# Battery_Pack_Protection.net
KiCad netlist of a schematic drawn in Altium Designer
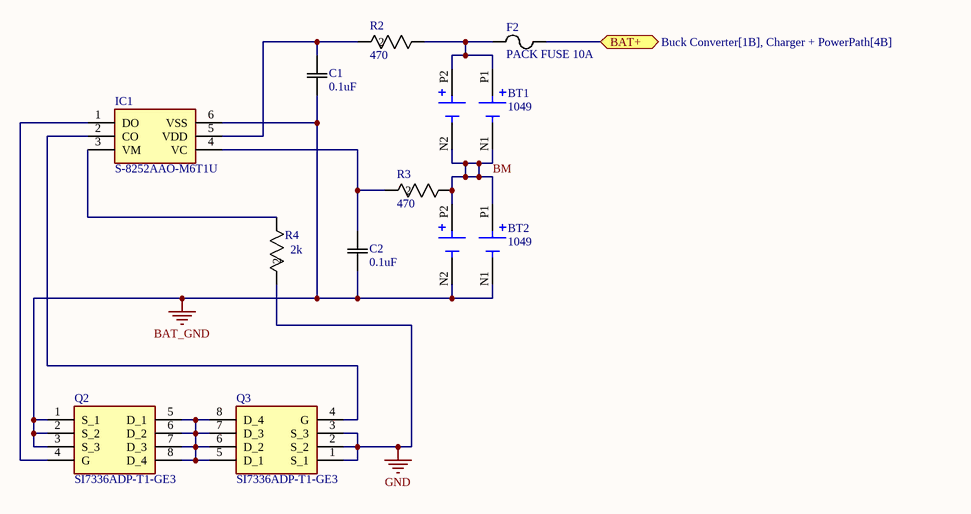
[diagram p0: Battery Pack + Protection.SchDoc]

(export (version "E")
  (design (tool "Eeschema 10.0.6"))
  (components
    (comp (ref "BT1")
      (value "1049")
      (footprint "BAT_1049")
      (description "THM Holder for Dual 18650 Batteries")
      (fields (field (name "MF") "Keystone Electronics"))
      (libsource (lib "1049") (part "1049"))
    )
    (comp (ref "BT2")
      (value "1049")
      (footprint "BAT_1049")
      (description "THM Holder for Dual 18650 Batteries")
      (fields (field (name "MF") "Keystone Electronics"))
      (libsource (lib "1049") (part "1049"))
    )
    (comp (ref "C1")
      (value "0.1uF")
      (footprint "CAPC220145_88N_KEM")
      (description "SMD Comm X7R, Ceramic, 0.1 uF, 10%, 50 VDC, X7R, SMD, MLCC, Temperature Stable, Class II, 0805")
      (fields
        (field (name "MANUFACTURER_PART_NUMBER") "C0805C104K5RACTU")
        (field (name "COPYRIGHT") "Copyright (C) 2025 Ultra Librarian. All rights reserved.")
      )
      (libsource (lib "C0805C104K5RACTU") (part "C0805C104K5RACTU"))
    )
    (comp (ref "C2")
      (value "0.1uF")
      (footprint "CAPC220145_88N_KEM")
      (description "SMD Comm X7R, Ceramic, 0.1 uF, 10%, 50 VDC, X7R, SMD, MLCC, Temperature Stable, Class II, 0805")
      (fields
        (field (name "MANUFACTURER_PART_NUMBER") "C0805C104K5RACTU")
        (field (name "COPYRIGHT") "Copyright (C) 2025 Ultra Librarian. All rights reserved.")
      )
      (libsource (lib "C0805C104K5RACTU") (part "C0805C104K5RACTU"))
    )
    (comp (ref "F2")
      (value "PACK FUSE 10A")
      (footprint "FUSE_2920L70012_LTF")
      (description "Description")
      (fields
        (field (name "MANUFACTURER_PART_NUMBER") "2920L700/12MR-A")
        (field (name "COPYRIGHT") "Copyright (C) 2025 Ultra Librarian. All rights reserved.")
      )
      (libsource (lib "2920L70012MR-A") (part "2920L70012MR-A"))
    )
    (comp (ref "IC1")
      (value "S-8252AAO-M6T1U")
      (footprint "SamacSys:SOT95P275X135-6N")
      (description "Integrated Circuit")
      (fields (field (name "MOUSER PART NUMBER") "628-S-8252AAO-M6T1U"))
      (libsource (lib "*") (part "S-8252AAO-M6T1U"))
    )
    (comp (ref "Q2")
      (value "SI7336ADP-T1-GE3")
      (footprint "SamacSys:SI7141DPT1GE3")
      (description "MOSFET (N-Channel)")
      (fields (field (name "MOUSER PART NUMBER") "781-SI7336ADP-GE3"))
      (libsource (lib "*") (part "SI7336ADP-T1-GE3"))
    )
    (comp (ref "Q3")
      (value "SI7336ADP-T1-GE3")
      (footprint "SamacSys:SI7141DPT1GE3")
      (description "MOSFET (N-Channel)")
      (fields (field (name "MOUSER PART NUMBER") "781-SI7336ADP-GE3"))
      (libsource (lib "") (part "SI7336ADP-T1-GE3_1"))
    )
    (comp (ref "R2")
      (value "470")
      (footprint "RC0805N_YAG")
      (description "Description")
      (fields
        (field (name "MANUFACTURER_PART_NUMBER") "RC0805FR-07470RL")
        (field (name "COPYRIGHT") "Copyright (C) 2025 Ultra Librarian. All rights reserved.")
      )
      (libsource (lib "RC0805FR-07470RL") (part "RC0805FR-07470RL"))
    )
    (comp (ref "R3")
      (value "470")
      (footprint "RC0805N_YAG")
      (description "Description")
      (fields
        (field (name "MANUFACTURER_PART_NUMBER") "RC0805FR-07470RL")
        (field (name "COPYRIGHT") "Copyright (C) 2025 Ultra Librarian. All rights reserved.")
      )
      (libsource (lib "RC0805FR-07470RL") (part "RC0805FR-07470RL"))
    )
    (comp (ref "R4")
      (value "2k")
      (footprint "RC0805N_YAG")
      (description "No Description Available")
      (fields
        (field (name "MANUFACTURER_PART_NUMBER") "RT0805FRE072KL")
        (field (name "COPYRIGHT") "Copyright (C) 2025 Ultra Librarian. All rights reserved.")
      )
      (libsource (lib "RT0805FRE072KL") (part "RT0805FRE072KL"))
    )
  )
  (nets
    (net (code "1") (name "/BAT+") (class "Default")
      (node (ref "F2") (pin "2") (pinfunction "2_2") (pintype "passive"))
    )
    (net (code "2") (name "/BM") (class "Default")
      (node (ref "BT1") (pin "N1") (pinfunction "NEG1_N1") (pintype "passive"))
      (node (ref "BT1") (pin "N2") (pinfunction "NEG2_N2") (pintype "passive"))
      (node (ref "BT2") (pin "P1") (pinfunction "POS1_P1") (pintype "passive"))
      (node (ref "BT2") (pin "P2") (pinfunction "POS2_P2") (pintype "passive"))
      (node (ref "R3") (pin "1") (pinfunction "1_1") (pintype "passive"))
    )
    (net (code "3") (name "BAT_GND") (class "Default")
      (node (ref "BT2") (pin "N1") (pinfunction "NEG1_N1") (pintype "passive"))
      (node (ref "BT2") (pin "N2") (pinfunction "NEG2_N2") (pintype "passive"))
      (node (ref "C1") (pin "1") (pinfunction "1_1") (pintype "passive"))
      (node (ref "C2") (pin "1") (pinfunction "1_1") (pintype "passive"))
      (node (ref "IC1") (pin "6") (pinfunction "VSS_6") (pintype "passive"))
      (node (ref "Q2") (pin "1") (pinfunction "S_1_1") (pintype "passive"))
      (node (ref "Q2") (pin "2") (pinfunction "S_2_2") (pintype "passive"))
      (node (ref "Q2") (pin "3") (pinfunction "S_3_3") (pintype "passive"))
    )
    (net (code "4") (name "GND") (class "Default")
      (node (ref "Q3") (pin "1") (pinfunction "S_1_1") (pintype "passive"))
      (node (ref "Q3") (pin "2") (pinfunction "S_2_2") (pintype "passive"))
      (node (ref "Q3") (pin "3") (pinfunction "S_3_3") (pintype "passive"))
      (node (ref "R4") (pin "2") (pinfunction "2_2") (pintype "passive"))
    )
    (net (code "5") (name "Net-(BT1-POS1)") (class "Default")
      (node (ref "BT1") (pin "P1") (pinfunction "POS1_P1") (pintype "passive"))
      (node (ref "BT1") (pin "P2") (pinfunction "POS2_P2") (pintype "passive"))
      (node (ref "F2") (pin "1") (pinfunction "1_1") (pintype "passive"))
      (node (ref "R2") (pin "1") (pinfunction "1_1") (pintype "passive"))
    )
    (net (code "6") (name "Net-(IC1-CO)") (class "Default")
      (node (ref "IC1") (pin "2") (pinfunction "CO_2") (pintype "passive"))
      (node (ref "Q3") (pin "4") (pinfunction "G_4") (pintype "passive"))
    )
    (net (code "7") (name "Net-(IC1-DO)") (class "Default")
      (node (ref "IC1") (pin "1") (pinfunction "DO_1") (pintype "passive"))
      (node (ref "Q2") (pin "4") (pinfunction "G_4") (pintype "passive"))
    )
    (net (code "8") (name "Net-(IC1-VC)") (class "Default")
      (node (ref "C2") (pin "2") (pinfunction "2_2") (pintype "passive"))
      (node (ref "IC1") (pin "4") (pinfunction "VC_4") (pintype "passive"))
      (node (ref "R3") (pin "2") (pinfunction "2_2") (pintype "passive"))
    )
    (net (code "9") (name "Net-(IC1-VDD)") (class "Default")
      (node (ref "C1") (pin "2") (pinfunction "2_2") (pintype "passive"))
      (node (ref "IC1") (pin "5") (pinfunction "VDD_5") (pintype "passive"))
      (node (ref "R2") (pin "2") (pinfunction "2_2") (pintype "passive"))
    )
    (net (code "10") (name "Net-(IC1-VM)") (class "Default")
      (node (ref "IC1") (pin "3") (pinfunction "VM_3") (pintype "passive"))
      (node (ref "R4") (pin "1") (pinfunction "1_1") (pintype "passive"))
    )
    (net (code "11") (name "Net-(Q2-D_1)") (class "Default")
      (node (ref "Q2") (pin "5") (pinfunction "D_1_5") (pintype "passive"))
      (node (ref "Q2") (pin "6") (pinfunction "D_2_6") (pintype "passive"))
      (node (ref "Q2") (pin "7") (pinfunction "D_3_7") (pintype "passive"))
      (node (ref "Q2") (pin "8") (pinfunction "D_4_8") (pintype "passive"))
      (node (ref "Q3") (pin "5") (pinfunction "D_1_5") (pintype "passive"))
      (node (ref "Q3") (pin "6") (pinfunction "D_2_6") (pintype "passive"))
      (node (ref "Q3") (pin "7") (pinfunction "D_3_7") (pintype "passive"))
      (node (ref "Q3") (pin "8") (pinfunction "D_4_8") (pintype "passive"))
    )
  )
)
